# Source.net
KiCad netlist of a schematic drawn in Altium Designer
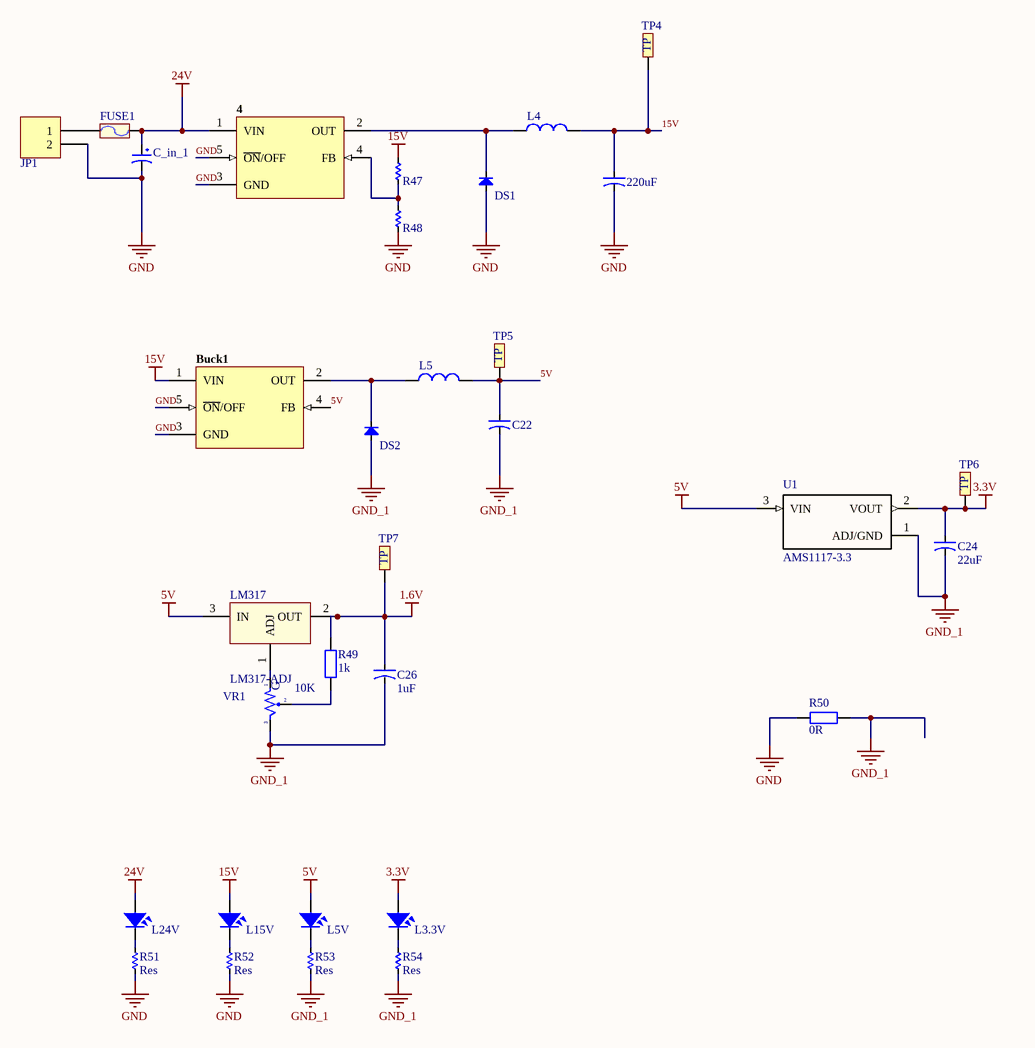
[diagram p0: Source.SchDoc]

(export (version "E")
  (design (tool "Eeschema 10.0.6"))
  (components
    (comp (ref "4") (value "LM2576-ADJ") (footprint "TO263") (libsource (lib "LIBRARY") (part "LM2576")))
    (comp (ref "220uF")
      (value "CN-ALU-DIP")
      (footprint "CA-ALU-5R")
      (description "Capacitor (Semiconductor SIM Model)")
      (fields (field (name "PUBLISHER") "Altium Limited"))
      (libsource (lib "LIBRARY") (part "CN-ALU-DIP"))
    )
    (comp (ref "Buck1") (value "LM2576-5V") (footprint "TO263") (libsource (lib "LIBRARY") (part "LM2576")))
    (comp (ref "C22")
      (value ">400uF")
      (footprint "CA-ALU-5R")
      (description "Capacitor (Semiconductor SIM Model)")
      (fields (field (name "PUBLISHER") "Altium Limited"))
      (libsource (lib "LIBRARY") (part "CN-ALU-DIP"))
    )
    (comp (ref "C24")
      (value "22uF")
      (footprint "CA-ALU-2.54")
      (description "Capacitor (Semiconductor SIM Model)")
      (fields (field (name "PUBLISHER") "Altium Limited"))
      (libsource (lib "LIBRARY") (part "CN-ALU-DIP"))
    )
    (comp (ref "C26")
      (value "1uF")
      (footprint "CA-ALU-2.54")
      (description "Capacitor (Semiconductor SIM Model)")
      (fields (field (name "PUBLISHER") "Altium Limited"))
      (libsource (lib "LIBRARY") (part "CN-ALU-DIP"))
    )
    (comp (ref "C_in_1")
      (value "100->220uF")
      (footprint "CP1.5/3.4")
      (description "Cap 1000uF/16V - 220uF/50V")
      (libsource (lib "syhaunguyen") (part "CP4"))
    )
    (comp (ref "DS1")
      (value "Diode")
      (footprint "DIO-1A")
      (description "Default Diode")
      (fields (field (name "PUBLISHER") "Altium Limited"))
      (libsource (lib "LIBRARY") (part "Diode"))
    )
    (comp (ref "DS2")
      (value "Diode")
      (footprint "DIO-1A")
      (description "Default Diode")
      (fields (field (name "PUBLISHER") "Altium Limited"))
      (libsource (lib "LIBRARY") (part "Diode"))
    )
    (comp (ref "FUSE1")
      (value "F1A")
      (footprint "Fuse1")
      (description "Fuse")
      (fields (field (name "DESIGNED BY") "VanDungEvn"))
      (libsource (lib "LIBRARY") (part "Fuse"))
    )
    (comp (ref "JP1")
      (value "Header 2_1")
      (footprint "HED2")
      (description "Header, 2-Pin")
      (fields (field (name "MANUFACTURER") "Generic Components"))
      (libsource (lib "syhaunguyen") (part "Header 2_1"))
    )
    (comp (ref "L3.3V")
      (value "LED")
      (footprint "LED-5-BLUE")
      (description "LED Single colour Green and Red")
      (libsource (lib "LIBRARY") (part "LED"))
    )
    (comp (ref "L4")
      (value "100uH")
      (footprint "L01")
      (description "Inductor")
      (libsource (lib "syhaunguyen") (part "L1"))
    )
    (comp (ref "L5")
      (value "~")
      (footprint "L01")
      (description "Inductor")
      (libsource (lib "syhaunguyen") (part "L1"))
    )
    (comp (ref "L5V")
      (value "LED")
      (footprint "LED-5-BLUE")
      (description "LED Single colour Green and Red")
      (libsource (lib "LIBRARY") (part "LED"))
    )
    (comp (ref "L15V")
      (value "LED")
      (footprint "LED-5-BLUE")
      (description "LED Single colour Green and Red")
      (libsource (lib "LIBRARY") (part "LED"))
    )
    (comp (ref "L24V")
      (value "LED")
      (footprint "LED-5-BLUE")
      (description "LED Single colour Green and Red")
      (libsource (lib "LIBRARY") (part "LED"))
    )
    (comp (ref "LM317")
      (value "LM317-ADJ")
      (footprint "TO220H3")
      (description "Adj Voltage +1.2 -> +37V")
      (libsource (lib "LIBRARY") (part "LM317"))
    )
    (comp (ref "R47")
      (value "20-24")
      (footprint "RES-1/2W")
      (description "Res")
      (fields
        (field (name "MANUFACTURER") "Generic Components")
        (field (name "PUBLISHER") "Altium Hobart Technology Centre")
      )
      (libsource (lib "LIBRARY") (part "Res"))
    )
    (comp (ref "R48")
      (value "2")
      (footprint "RES-1/2W")
      (description "Res")
      (fields
        (field (name "MANUFACTURER") "Generic Components")
        (field (name "PUBLISHER") "Altium Hobart Technology Centre")
      )
      (libsource (lib "LIBRARY") (part "Res"))
    )
    (comp (ref "R49")
      (value "1k")
      (footprint "R1/4W")
      (description "Resistor 1/4W")
      (libsource (lib "syhaunguyen") (part "R1/4W"))
    )
    (comp (ref "R50")
      (value "0R")
      (footprint "R1/4W")
      (description "Resistor 1/4W")
      (libsource (lib "syhaunguyen") (part "R1/4W"))
    )
    (comp (ref "R51")
      (value "Res")
      (footprint "RES-1/2W")
      (fields
        (field (name "MANUFACTURER") "Generic Components")
        (field (name "PUBLISHER") "Altium Hobart Technology Centre")
      )
      (libsource (lib "LIBRARY1") (part "Res"))
    )
    (comp (ref "R52")
      (value "Res")
      (footprint "RES-1/2W")
      (fields
        (field (name "MANUFACTURER") "Generic Components")
        (field (name "PUBLISHER") "Altium Hobart Technology Centre")
      )
      (libsource (lib "LIBRARY1") (part "Res"))
    )
    (comp (ref "R53")
      (value "Res")
      (footprint "RES-1/2W")
      (fields
        (field (name "MANUFACTURER") "Generic Components")
        (field (name "PUBLISHER") "Altium Hobart Technology Centre")
      )
      (libsource (lib "LIBRARY1") (part "Res"))
    )
    (comp (ref "R54")
      (value "Res")
      (footprint "RES-1/2W")
      (fields
        (field (name "MANUFACTURER") "Generic Components")
        (field (name "PUBLISHER") "Altium Hobart Technology Centre")
      )
      (libsource (lib "LIBRARY1") (part "Res"))
    )
    (comp (ref "TP4")
      (value "~")
      (footprint "TP")
      (description "CONNECT 1")
      (libsource (lib "syhaunguyen") (part "TP"))
    )
    (comp (ref "TP5")
      (value "~")
      (footprint "TP")
      (description "CONNECT 1")
      (libsource (lib "syhaunguyen") (part "TP"))
    )
    (comp (ref "TP6")
      (value "~")
      (footprint "TP")
      (description "CONNECT 1")
      (libsource (lib "syhaunguyen") (part "TP"))
    )
    (comp (ref "TP7")
      (value "~")
      (footprint "TP")
      (description "CONNECT 1")
      (libsource (lib "syhaunguyen") (part "TP"))
    )
    (comp (ref "U1")
      (value "AMS1117-3.3")
      (footprint "*SOT229P700X180-4N")
      (description "Sot223/Pkg 1-Amp 3.3-Volt Low Drop Out Voltage Regulatator")
      (fields (field (name "MF") "Advanced Monolithic Systems"))
      (libsource (lib "SemacSYS") (part "AMS1117-3.3"))
    )
    (comp (ref "VR1")
      (value "10K")
      (footprint "VR-S2")
      (description "Var Resistor")
      (libsource (lib "LIBRARY1") (part "VR-S"))
    )
  )
  (nets
    (net (code "1") (name "1.6V") (class "Default")
      (node (ref "C26") (pin "1") (pinfunction "1_1") (pintype "passive"))
      (node (ref "LM317") (pin "2") (pinfunction "OUT_2") (pintype "passive"))
      (node (ref "R49") (pin "2") (pinfunction "2_2") (pintype "passive"))
      (node (ref "TP7") (pin "TP1") (pinfunction "0_TP1") (pintype "passive"))
    )
    (net (code "2") (name "3.3V") (class "Default")
      (node (ref "C24") (pin "1") (pinfunction "1_1") (pintype "passive"))
      (node (ref "L3.3V") (pin "1") (pinfunction "1_1") (pintype "passive"))
      (node (ref "TP6") (pin "TP1") (pinfunction "0_TP1") (pintype "passive"))
      (node (ref "U1") (pin "2") (pinfunction "VOUT_2") (pintype "output"))
    )
    (net (code "3") (name "5V") (class "Default")
      (node (ref "Buck1") (pin "4") (pinfunction "FB_4") (pintype "input"))
      (node (ref "C22") (pin "1") (pinfunction "1_1") (pintype "passive"))
      (node (ref "L5") (pin "2") (pinfunction "2_2") (pintype "passive"))
      (node (ref "L5V") (pin "1") (pinfunction "1_1") (pintype "passive"))
      (node (ref "LM317") (pin "3") (pinfunction "IN_3") (pintype "passive"))
      (node (ref "TP5") (pin "TP1") (pinfunction "0_TP1") (pintype "passive"))
      (node (ref "U1") (pin "3") (pinfunction "VIN_3") (pintype "input"))
    )
    (net (code "4") (name "15V") (class "Default")
      (node (ref "220uF") (pin "1") (pinfunction "1_1") (pintype "passive"))
      (node (ref "Buck1") (pin "1") (pinfunction "VIN_1") (pintype "power_in"))
      (node (ref "L15V") (pin "1") (pinfunction "1_1") (pintype "passive"))
      (node (ref "L4") (pin "2") (pinfunction "2_2") (pintype "passive"))
      (node (ref "R47") (pin "1") (pinfunction "1_1") (pintype "passive"))
      (node (ref "TP4") (pin "TP1") (pinfunction "0_TP1") (pintype "passive"))
    )
    (net (code "5") (name "24V") (class "Default")
      (node (ref "4") (pin "1") (pinfunction "VIN_1") (pintype "power_in"))
      (node (ref "C_in_1") (pin "1") (pinfunction "1_1") (pintype "passive"))
      (node (ref "FUSE1") (pin "2") (pinfunction "2_2") (pintype "passive"))
      (node (ref "L24V") (pin "1") (pinfunction "1_1") (pintype "passive"))
    )
    (net (code "6") (name "GND") (class "Default")
      (node (ref "220uF") (pin "2") (pinfunction "2_2") (pintype "passive"))
      (node (ref "4") (pin "3") (pinfunction "GND_3") (pintype "power_in"))
      (node (ref "4") (pin "5") (pinfunction "~{ON}/OFF_5") (pintype "input"))
      (node (ref "Buck1") (pin "3") (pinfunction "GND_3") (pintype "power_in"))
      (node (ref "Buck1") (pin "5") (pinfunction "~{ON}/OFF_5") (pintype "input"))
      (node (ref "C_in_1") (pin "2") (pinfunction "2_2") (pintype "passive"))
      (node (ref "DS1") (pin "1") (pinfunction "A_1") (pintype "passive"))
      (node (ref "JP1") (pin "2") (pinfunction "2_2") (pintype "passive"))
      (node (ref "R48") (pin "2") (pinfunction "2_2") (pintype "passive"))
      (node (ref "R50") (pin "2") (pinfunction "2_2") (pintype "passive"))
      (node (ref "R51") (pin "2") (pinfunction "2_2") (pintype "passive"))
      (node (ref "R52") (pin "2") (pinfunction "2_2") (pintype "passive"))
    )
    (net (code "7") (name "GND_1") (class "Default")
      (node (ref "C22") (pin "2") (pinfunction "2_2") (pintype "passive"))
      (node (ref "C24") (pin "2") (pinfunction "2_2") (pintype "passive"))
      (node (ref "C26") (pin "2") (pinfunction "2_2") (pintype "passive"))
      (node (ref "DS2") (pin "1") (pinfunction "A_1") (pintype "passive"))
      (node (ref "R50") (pin "1") (pinfunction "1_1") (pintype "passive"))
      (node (ref "R53") (pin "2") (pinfunction "2_2") (pintype "passive"))
      (node (ref "R54") (pin "2") (pinfunction "2_2") (pintype "passive"))
      (node (ref "U1") (pin "1") (pinfunction "ADJ/GND_1") (pintype "power_in"))
      (node (ref "VR1") (pin "3") (pinfunction "3_3") (pintype "passive"))
    )
    (net (code "8") (name "Net-(4-FB)") (class "Default")
      (node (ref "4") (pin "4") (pinfunction "FB_4") (pintype "input"))
      (node (ref "R47") (pin "2") (pinfunction "2_2") (pintype "passive"))
      (node (ref "R48") (pin "1") (pinfunction "1_1") (pintype "passive"))
    )
    (net (code "9") (name "Net-(4-OUT)") (class "Default")
      (node (ref "4") (pin "2") (pinfunction "OUT_2") (pintype "power_in"))
      (node (ref "DS1") (pin "2") (pinfunction "K_2") (pintype "passive"))
      (node (ref "L4") (pin "1") (pinfunction "1_1") (pintype "passive"))
    )
    (net (code "10") (name "Net-(Buck1-OUT)") (class "Default")
      (node (ref "Buck1") (pin "2") (pinfunction "OUT_2") (pintype "power_in"))
      (node (ref "DS2") (pin "2") (pinfunction "K_2") (pintype "passive"))
      (node (ref "L5") (pin "1") (pinfunction "1_1") (pintype "passive"))
    )
    (net (code "11") (name "Net-(FUSE1-Pad1)") (class "Default")
      (node (ref "FUSE1") (pin "1") (pinfunction "1_1") (pintype "passive"))
      (node (ref "JP1") (pin "1") (pinfunction "1_1") (pintype "passive"))
    )
    (net (code "12") (name "Net-(L3.3V-Pad2)") (class "Default")
      (node (ref "L3.3V") (pin "2") (pinfunction "2_2") (pintype "passive"))
      (node (ref "R54") (pin "1") (pinfunction "1_1") (pintype "passive"))
    )
    (net (code "13") (name "Net-(L5V-Pad2)") (class "Default")
      (node (ref "L5V") (pin "2") (pinfunction "2_2") (pintype "passive"))
      (node (ref "R53") (pin "1") (pinfunction "1_1") (pintype "passive"))
    )
    (net (code "14") (name "Net-(L15V-Pad2)") (class "Default")
      (node (ref "L15V") (pin "2") (pinfunction "2_2") (pintype "passive"))
      (node (ref "R52") (pin "1") (pinfunction "1_1") (pintype "passive"))
    )
    (net (code "15") (name "Net-(L24V-Pad2)") (class "Default")
      (node (ref "L24V") (pin "2") (pinfunction "2_2") (pintype "passive"))
      (node (ref "R51") (pin "1") (pinfunction "1_1") (pintype "passive"))
    )
    (net (code "16") (name "Net-(LM317-ADJ)") (class "Default")
      (node (ref "LM317") (pin "1") (pinfunction "ADJ_1") (pintype "passive"))
      (node (ref "VR1") (pin "1") (pinfunction "1_1") (pintype "passive"))
    )
    (net (code "17") (name "Net-(R49-Pad1)") (class "Default")
      (node (ref "R49") (pin "1") (pinfunction "1_1") (pintype "passive"))
      (node (ref "VR1") (pin "2") (pinfunction "2_2") (pintype "passive"))
    )
  )
)
